# ADE7763_Breakout.net
KiCad netlist of a schematic drawn in EAGLE
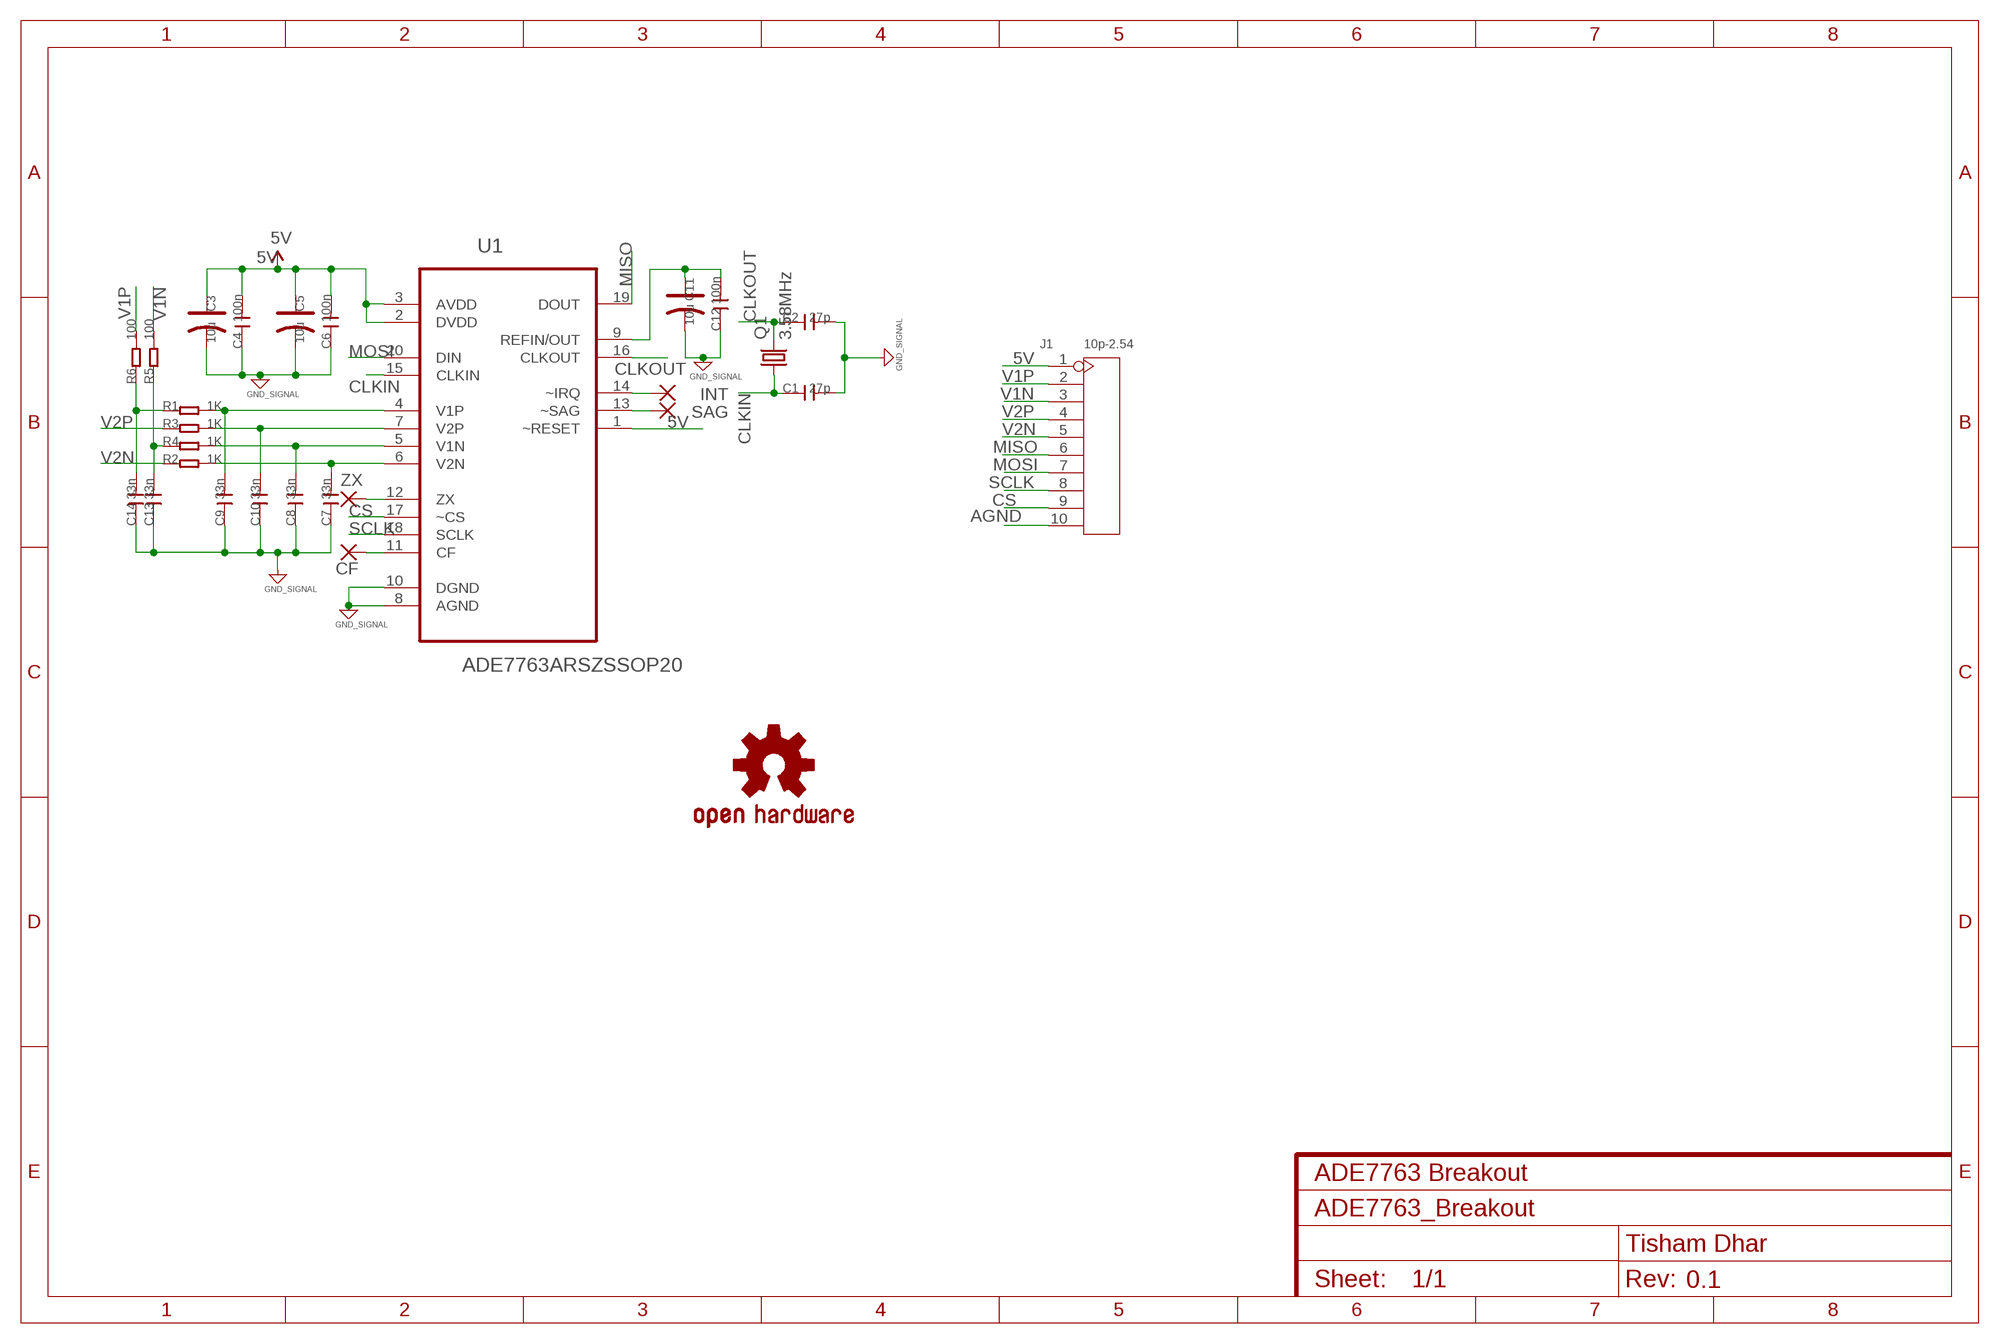
[diagram p0: schematic, sheet 1]

(export (version "E")
  (design (tool "Eeschema 10.0.6"))
  (components
    (comp (ref "C1")
      (value "27p")
      (footprint "eagle-import:C0603")
      (libsource (lib "eagle-import") (part "C-0603"))
    )
    (comp (ref "C2")
      (value "27p")
      (footprint "eagle-import:C0603")
      (libsource (lib "eagle-import") (part "C-0603"))
    )
    (comp (ref "C3")
      (value "10u")
      (footprint "eagle-import:AVX-A")
      (libsource (lib "eagle-import") (part "CAP-AVX-A"))
    )
    (comp (ref "C4")
      (value "100n")
      (footprint "eagle-import:C0603")
      (libsource (lib "eagle-import") (part "C-0603"))
    )
    (comp (ref "C5")
      (value "10u")
      (footprint "eagle-import:AVX-A")
      (libsource (lib "eagle-import") (part "CAP-AVX-A"))
    )
    (comp (ref "C6")
      (value "100n")
      (footprint "eagle-import:C0603")
      (libsource (lib "eagle-import") (part "C-0603"))
    )
    (comp (ref "C7")
      (value "33n")
      (footprint "eagle-import:C0603")
      (libsource (lib "eagle-import") (part "C-0603"))
    )
    (comp (ref "C8")
      (value "33n")
      (footprint "eagle-import:C0603")
      (libsource (lib "eagle-import") (part "C-0603"))
    )
    (comp (ref "C9")
      (value "33n")
      (footprint "eagle-import:C0603")
      (libsource (lib "eagle-import") (part "C-0603"))
    )
    (comp (ref "C10")
      (value "33n")
      (footprint "eagle-import:C0603")
      (libsource (lib "eagle-import") (part "C-0603"))
    )
    (comp (ref "C11")
      (value "10u")
      (footprint "eagle-import:AVX-A")
      (libsource (lib "eagle-import") (part "CAP-AVX-A"))
    )
    (comp (ref "C12")
      (value "100n")
      (footprint "eagle-import:C0603")
      (libsource (lib "eagle-import") (part "C-0603"))
    )
    (comp (ref "C13")
      (value "33n")
      (footprint "eagle-import:C0603")
      (libsource (lib "eagle-import") (part "C-0603"))
    )
    (comp (ref "C14")
      (value "33n")
      (footprint "eagle-import:C0603")
      (libsource (lib "eagle-import") (part "C-0603"))
    )
    (comp (ref "CF")
      (value "WIREPADSMD1,27-254")
      (footprint "eagle-import:SMD1,27-2,54")
      (libsource (lib "eagle-import") (part "WIREPADSMD1,27-254"))
    )
    (comp (ref "INT")
      (value "WIREPADSMD1,27-254")
      (footprint "eagle-import:SMD1,27-2,54")
      (libsource (lib "eagle-import") (part "WIREPADSMD1,27-254"))
    )
    (comp (ref "J1")
      (value "10p-2.54")
      (footprint "eagle-import:H10-2.54")
      (fields (field (name "MPN") "P125-1110A0BS116AX"))
      (libsource (lib "eagle-import") (part "DIP-BLACK-MALE-HEADER-VERT(10P-2.54)"))
    )
    (comp (ref "LOGO1")
      (value "OSHW-LOGOM")
      (footprint "eagle-import:OSHW-LOGO-M")
      (libsource (lib "eagle-import") (part "OSHW-LOGOM"))
    )
    (comp (ref "Q1")
      (value "3.58MHz")
      (footprint "eagle-import:HC49UP")
      (libsource (lib "eagle-import") (part "CRYSTALHC49UP"))
    )
    (comp (ref "R1")
      (value "1K")
      (footprint "eagle-import:R0603")
      (libsource (lib "eagle-import") (part "R-0603"))
    )
    (comp (ref "R2")
      (value "1K")
      (footprint "eagle-import:R0603")
      (libsource (lib "eagle-import") (part "R-0603"))
    )
    (comp (ref "R3")
      (value "1K")
      (footprint "eagle-import:R0603")
      (libsource (lib "eagle-import") (part "R-0603"))
    )
    (comp (ref "R4")
      (value "1K")
      (footprint "eagle-import:R0603")
      (libsource (lib "eagle-import") (part "R-0603"))
    )
    (comp (ref "R5")
      (value "100")
      (footprint "eagle-import:R0603")
      (libsource (lib "eagle-import") (part "R-0603"))
    )
    (comp (ref "R6")
      (value "100")
      (footprint "eagle-import:R0603")
      (libsource (lib "eagle-import") (part "R-0603"))
    )
    (comp (ref "SAG")
      (value "WIREPADSMD1,27-254")
      (footprint "eagle-import:SMD1,27-2,54")
      (libsource (lib "eagle-import") (part "WIREPADSMD1,27-254"))
    )
    (comp (ref "U1")
      (value "ADE7763ARSZSSOP20")
      (footprint "eagle-import:RS_20-M")
      (libsource (lib "eagle-import") (part "ADE7763ARSZSSOP20"))
    )
    (comp (ref "ZX")
      (value "WIREPADSMD1,27-254")
      (footprint "eagle-import:SMD1,27-2,54")
      (libsource (lib "eagle-import") (part "WIREPADSMD1,27-254"))
    )
  )
  (nets
    (net (code "1") (name "/CLKIN") (class "Default")
      (node (ref "C1") (pin "1") (pinfunction "1_1") (pintype "passive"))
      (node (ref "Q1") (pin "1") (pinfunction "1_1") (pintype "passive"))
      (node (ref "U1") (pin "15") (pinfunction "CLKIN_15") (pintype "input"))
    )
    (net (code "2") (name "/CLKOUT") (class "Default")
      (node (ref "C2") (pin "1") (pinfunction "1_1") (pintype "passive"))
      (node (ref "Q1") (pin "2") (pinfunction "2_2") (pintype "passive"))
      (node (ref "U1") (pin "16") (pinfunction "CLKOUT_16") (pintype "output"))
    )
    (net (code "3") (name "/CS") (class "Default")
      (node (ref "J1") (pin "9") (pinfunction "9_9") (pintype "bidirectional"))
      (node (ref "U1") (pin "17") (pinfunction "~{CS}_17") (pintype "input"))
    )
    (net (code "4") (name "/MISO") (class "Default")
      (node (ref "J1") (pin "6") (pinfunction "6_6") (pintype "bidirectional"))
      (node (ref "U1") (pin "19") (pinfunction "DOUT_19") (pintype "output"))
    )
    (net (code "5") (name "/MOSI") (class "Default")
      (node (ref "J1") (pin "7") (pinfunction "7_7") (pintype "bidirectional"))
      (node (ref "U1") (pin "20") (pinfunction "DIN_20") (pintype "input"))
    )
    (net (code "6") (name "/SCLK") (class "Default")
      (node (ref "J1") (pin "8") (pinfunction "8_8") (pintype "bidirectional"))
      (node (ref "U1") (pin "18") (pinfunction "SCLK_18") (pintype "input"))
    )
    (net (code "7") (name "/V1N") (class "Default")
      (node (ref "J1") (pin "3") (pinfunction "3_3") (pintype "bidirectional"))
      (node (ref "R5") (pin "2") (pinfunction "2_2") (pintype "passive"))
    )
    (net (code "8") (name "/V1P") (class "Default")
      (node (ref "J1") (pin "2") (pinfunction "2_2") (pintype "bidirectional"))
      (node (ref "R6") (pin "2") (pinfunction "2_2") (pintype "passive"))
    )
    (net (code "9") (name "/V2N") (class "Default")
      (node (ref "J1") (pin "5") (pinfunction "5_5") (pintype "bidirectional"))
      (node (ref "R2") (pin "1") (pinfunction "1_1") (pintype "passive"))
    )
    (net (code "10") (name "/V2P") (class "Default")
      (node (ref "J1") (pin "4") (pinfunction "4_4") (pintype "bidirectional"))
      (node (ref "R3") (pin "1") (pinfunction "1_1") (pintype "passive"))
    )
    (net (code "11") (name "5V") (class "Default")
      (node (ref "C3") (pin "+") (pinfunction "+_+") (pintype "passive"))
      (node (ref "C4") (pin "2") (pinfunction "2_2") (pintype "passive"))
      (node (ref "C5") (pin "+") (pinfunction "+_+") (pintype "passive"))
      (node (ref "C6") (pin "2") (pinfunction "2_2") (pintype "passive"))
      (node (ref "J1") (pin "1") (pinfunction "1_1") (pintype "bidirectional"))
      (node (ref "U1") (pin "1") (pinfunction "~{RESET}_1") (pintype "output"))
      (node (ref "U1") (pin "2") (pinfunction "DVDD_2") (pintype "power_in"))
      (node (ref "U1") (pin "3") (pinfunction "AVDD_3") (pintype "power_in"))
    )
    (net (code "12") (name "GND_SIGNAL") (class "Default")
      (node (ref "C1") (pin "2") (pinfunction "2_2") (pintype "passive"))
      (node (ref "C10") (pin "1") (pinfunction "1_1") (pintype "passive"))
      (node (ref "C11") (pin "-") (pinfunction "-_-") (pintype "passive"))
      (node (ref "C12") (pin "1") (pinfunction "1_1") (pintype "passive"))
      (node (ref "C13") (pin "1") (pinfunction "1_1") (pintype "passive"))
      (node (ref "C14") (pin "1") (pinfunction "1_1") (pintype "passive"))
      (node (ref "C2") (pin "2") (pinfunction "2_2") (pintype "passive"))
      (node (ref "C3") (pin "-") (pinfunction "-_-") (pintype "passive"))
      (node (ref "C4") (pin "1") (pinfunction "1_1") (pintype "passive"))
      (node (ref "C5") (pin "-") (pinfunction "-_-") (pintype "passive"))
      (node (ref "C6") (pin "1") (pinfunction "1_1") (pintype "passive"))
      (node (ref "C7") (pin "1") (pinfunction "1_1") (pintype "passive"))
      (node (ref "C8") (pin "1") (pinfunction "1_1") (pintype "passive"))
      (node (ref "C9") (pin "1") (pinfunction "1_1") (pintype "passive"))
      (node (ref "J1") (pin "10") (pinfunction "10_10") (pintype "bidirectional"))
      (node (ref "U1") (pin "10") (pinfunction "DGND_10") (pintype "passive"))
      (node (ref "U1") (pin "8") (pinfunction "AGND_8") (pintype "passive"))
    )
    (net (code "13") (name "Net-(C13-Pad2)") (class "Default")
      (node (ref "C13") (pin "2") (pinfunction "2_2") (pintype "passive"))
      (node (ref "R4") (pin "1") (pinfunction "1_1") (pintype "passive"))
      (node (ref "R5") (pin "1") (pinfunction "1_1") (pintype "passive"))
    )
    (net (code "14") (name "Net-(C14-Pad2)") (class "Default")
      (node (ref "C14") (pin "2") (pinfunction "2_2") (pintype "passive"))
      (node (ref "R1") (pin "1") (pinfunction "1_1") (pintype "passive"))
      (node (ref "R6") (pin "1") (pinfunction "1_1") (pintype "passive"))
    )
    (net (code "15") (name "Net-(CF-P)") (class "Default")
      (node (ref "CF") (pin "1") (pinfunction "P_1") (pintype "passive"))
      (node (ref "U1") (pin "11") (pinfunction "CF_11") (pintype "input"))
    )
    (net (code "16") (name "Net-(INT-P)") (class "Default")
      (node (ref "INT") (pin "1") (pinfunction "P_1") (pintype "passive"))
      (node (ref "U1") (pin "14") (pinfunction "~{IRQ}_14") (pintype "output"))
    )
    (net (code "17") (name "Net-(SAG-P)") (class "Default")
      (node (ref "SAG") (pin "1") (pinfunction "P_1") (pintype "passive"))
      (node (ref "U1") (pin "13") (pinfunction "~{SAG}_13") (pintype "output"))
    )
    (net (code "18") (name "Net-(U1-REFIN{slash}OUT)") (class "Default")
      (node (ref "C11") (pin "+") (pinfunction "+_+") (pintype "passive"))
      (node (ref "C12") (pin "2") (pinfunction "2_2") (pintype "passive"))
      (node (ref "U1") (pin "9") (pinfunction "REFIN/OUT_9") (pintype "bidirectional"))
    )
    (net (code "19") (name "Net-(U1-V1N)") (class "Default")
      (node (ref "C8") (pin "2") (pinfunction "2_2") (pintype "passive"))
      (node (ref "R4") (pin "2") (pinfunction "2_2") (pintype "passive"))
      (node (ref "U1") (pin "5") (pinfunction "V1N_5") (pintype "input"))
    )
    (net (code "20") (name "Net-(U1-V1P)") (class "Default")
      (node (ref "C9") (pin "2") (pinfunction "2_2") (pintype "passive"))
      (node (ref "R1") (pin "2") (pinfunction "2_2") (pintype "passive"))
      (node (ref "U1") (pin "4") (pinfunction "V1P_4") (pintype "input"))
    )
    (net (code "21") (name "Net-(U1-V2N)") (class "Default")
      (node (ref "C7") (pin "2") (pinfunction "2_2") (pintype "passive"))
      (node (ref "R2") (pin "2") (pinfunction "2_2") (pintype "passive"))
      (node (ref "U1") (pin "6") (pinfunction "V2N_6") (pintype "input"))
    )
    (net (code "22") (name "Net-(U1-V2P)") (class "Default")
      (node (ref "C10") (pin "2") (pinfunction "2_2") (pintype "passive"))
      (node (ref "R3") (pin "2") (pinfunction "2_2") (pintype "passive"))
      (node (ref "U1") (pin "7") (pinfunction "V2P_7") (pintype "input"))
    )
    (net (code "23") (name "Net-(U1-ZX)") (class "Default")
      (node (ref "U1") (pin "12") (pinfunction "ZX_12") (pintype "input"))
      (node (ref "ZX") (pin "1") (pinfunction "P_1") (pintype "passive"))
    )
  )
)
